# usbc-test.net
KiCad netlist of a schematic drawn in EAGLE
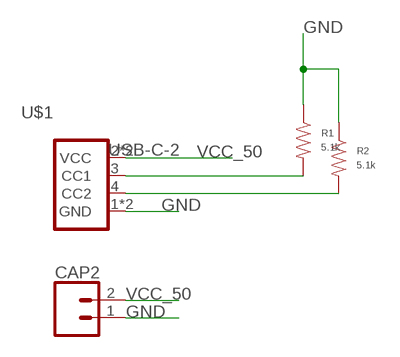
[diagram p0: schematic, sheet 1]

(export (version "E")
  (design (tool "Eeschema 10.0.6"))
  (components
    (comp (ref "CAP2")
      (value "CONN_02")
      (footprint "eagle-import:1X02")
      (libsource (lib "eagle-import") (part "CONN_02"))
    )
    (comp (ref "R1")
      (value "5.1k")
      (footprint "eagle-import:R0603")
      (libsource (lib "eagle-import") (part "RESISTOR_0603"))
    )
    (comp (ref "R2")
      (value "5.1k")
      (footprint "eagle-import:R0603")
      (libsource (lib "eagle-import") (part "RESISTOR_0603"))
    )
    (comp (ref "U$1")
      (value "USB-C-2")
      (footprint "eagle-import:USB-C-16")
      (libsource (lib "eagle-import") (part "USB-C-2"))
    )
  )
  (nets
    (net (code "1") (name "/GND") (class "Default")
      (node (ref "CAP2") (pin "1") (pinfunction "1_1") (pintype "passive"))
      (node (ref "R1") (pin "P$1") (pinfunction "P$1_P$1") (pintype "passive"))
      (node (ref "R2") (pin "P$1") (pinfunction "P$1_P$1") (pintype "passive"))
      (node (ref "U$1") (pin "1") (pinfunction "GND_1") (pintype "power_in"))
      (node (ref "U$1") (pin "6") (pinfunction "GND_6") (pintype "power_in"))
    )
    (net (code "2") (name "/VCC_50") (class "Default")
      (node (ref "CAP2") (pin "2") (pinfunction "2_2") (pintype "passive"))
      (node (ref "U$1") (pin "2") (pinfunction "VCC_2") (pintype "power_in"))
      (node (ref "U$1") (pin "5") (pinfunction "VCC_5") (pintype "power_in"))
    )
    (net (code "3") (name "Net-(U$1-CC1)") (class "Default")
      (node (ref "R1") (pin "P$2") (pinfunction "P$2_P$2") (pintype "passive"))
      (node (ref "U$1") (pin "3") (pinfunction "CC1_3") (pintype "bidirectional"))
    )
    (net (code "4") (name "Net-(U$1-CC2)") (class "Default")
      (node (ref "R2") (pin "P$2") (pinfunction "P$2_P$2") (pintype "passive"))
      (node (ref "U$1") (pin "4") (pinfunction "CC2_4") (pintype "bidirectional"))
    )
  )
)
